# covox.net
KiCad netlist of a schematic drawn in EAGLE
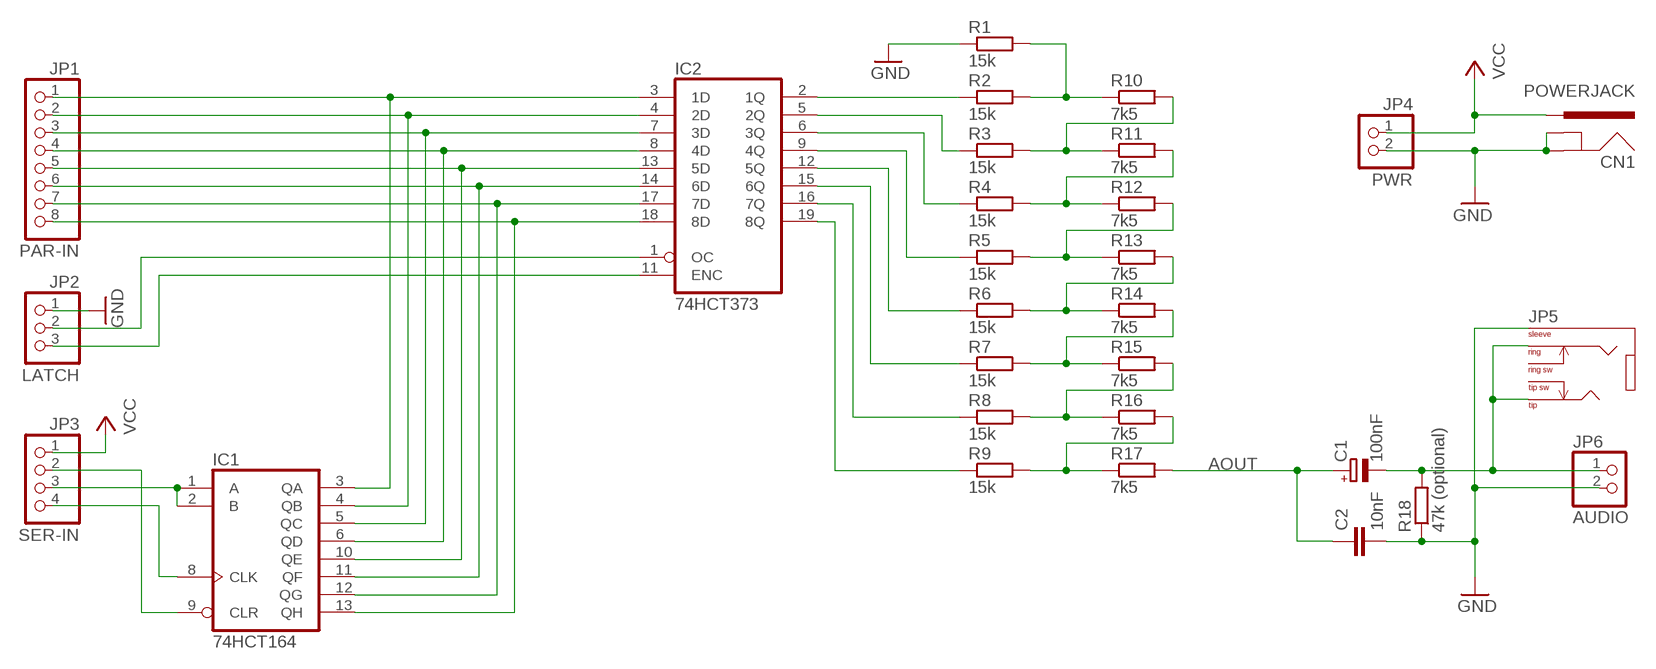
[diagram p0: schematic, sheet 1]

(export (version "E")
  (design (tool "Eeschema 10.0.6"))
  (components
    (comp (ref "C1")
      (value "100nF")
      (footprint "eagle-import:E2-4")
      (libsource (lib "eagle-import") (part "CPOL-EUE2-4"))
    )
    (comp (ref "C2")
      (value "10nF")
      (footprint "eagle-import:C025-025X050")
      (libsource (lib "eagle-import") (part "C-EU025-025X050"))
    )
    (comp (ref "CN1")
      (value "POWERJACK")
      (footprint "eagle-import:POWERJACK_SLOT")
      (libsource (lib "eagle-import") (part "POWERJACK-SLOT"))
    )
    (comp (ref "IC1")
      (value "74HCT164")
      (footprint "eagle-import:DIL14")
      (libsource (lib "eagle-import") (part "74164NHC"))
    )
    (comp (ref "IC2")
      (value "74HCT373")
      (footprint "eagle-import:DIL20")
      (libsource (lib "eagle-import") (part "74373NHCT"))
    )
    (comp (ref "JP1")
      (value "PAR-IN")
      (footprint "eagle-import:1X08")
      (libsource (lib "eagle-import") (part "PINHD-1X8"))
    )
    (comp (ref "JP2")
      (value "LATCH")
      (footprint "eagle-import:1X03")
      (libsource (lib "eagle-import") (part "PINHD-1X3"))
    )
    (comp (ref "JP3")
      (value "SER-IN")
      (footprint "eagle-import:1X04")
      (libsource (lib "eagle-import") (part "PINHD-1X4"))
    )
    (comp (ref "JP4")
      (value "PWR")
      (footprint "eagle-import:1X02")
      (libsource (lib "eagle-import") (part "PINHD-1X2"))
    )
    (comp (ref "JP5")
      (value "AUDIO")
      (footprint "eagle-import:AUDIO-JACK-3.5MM")
      (libsource (lib "eagle-import") (part "AUDIO-JACK-3.5MM"))
    )
    (comp (ref "JP6")
      (value "AUDIO")
      (footprint "eagle-import:1X02")
      (libsource (lib "eagle-import") (part "PINHD-1X2"))
    )
    (comp (ref "R1")
      (value "15k")
      (footprint "eagle-import:0204_7")
      (libsource (lib "eagle-import") (part "R-EU_0204/7"))
    )
    (comp (ref "R2")
      (value "15k")
      (footprint "eagle-import:0204_7")
      (libsource (lib "eagle-import") (part "R-EU_0204/7"))
    )
    (comp (ref "R3")
      (value "15k")
      (footprint "eagle-import:0204_7")
      (libsource (lib "eagle-import") (part "R-EU_0204/7"))
    )
    (comp (ref "R4")
      (value "15k")
      (footprint "eagle-import:0204_7")
      (libsource (lib "eagle-import") (part "R-EU_0204/7"))
    )
    (comp (ref "R5")
      (value "15k")
      (footprint "eagle-import:0204_7")
      (libsource (lib "eagle-import") (part "R-EU_0204/7"))
    )
    (comp (ref "R6")
      (value "15k")
      (footprint "eagle-import:0204_7")
      (libsource (lib "eagle-import") (part "R-EU_0204/7"))
    )
    (comp (ref "R7")
      (value "15k")
      (footprint "eagle-import:0204_7")
      (libsource (lib "eagle-import") (part "R-EU_0204/7"))
    )
    (comp (ref "R8")
      (value "15k")
      (footprint "eagle-import:0204_7")
      (libsource (lib "eagle-import") (part "R-EU_0204/7"))
    )
    (comp (ref "R9")
      (value "15k")
      (footprint "eagle-import:0204_7")
      (libsource (lib "eagle-import") (part "R-EU_0204/7"))
    )
    (comp (ref "R10")
      (value "7k5")
      (footprint "eagle-import:0204_7")
      (libsource (lib "eagle-import") (part "R-EU_0204/7"))
    )
    (comp (ref "R11")
      (value "7k5")
      (footprint "eagle-import:0204_7")
      (libsource (lib "eagle-import") (part "R-EU_0204/7"))
    )
    (comp (ref "R12")
      (value "7k5")
      (footprint "eagle-import:0204_7")
      (libsource (lib "eagle-import") (part "R-EU_0204/7"))
    )
    (comp (ref "R13")
      (value "7k5")
      (footprint "eagle-import:0204_7")
      (libsource (lib "eagle-import") (part "R-EU_0204/7"))
    )
    (comp (ref "R14")
      (value "7k5")
      (footprint "eagle-import:0204_7")
      (libsource (lib "eagle-import") (part "R-EU_0204/7"))
    )
    (comp (ref "R15")
      (value "7k5")
      (footprint "eagle-import:0204_7")
      (libsource (lib "eagle-import") (part "R-EU_0204/7"))
    )
    (comp (ref "R16")
      (value "7k5")
      (footprint "eagle-import:0204_7")
      (libsource (lib "eagle-import") (part "R-EU_0204/7"))
    )
    (comp (ref "R17")
      (value "7k5")
      (footprint "eagle-import:0204_7")
      (libsource (lib "eagle-import") (part "R-EU_0204/7"))
    )
    (comp (ref "R18")
      (value "47k (optional)")
      (footprint "eagle-import:0204_7")
      (libsource (lib "eagle-import") (part "R-EU_0204/7"))
    )
  )
  (nets
    (net (code "1") (name "/AOUT") (class "Default")
      (node (ref "C1") (pin "+") (pinfunction "+_+") (pintype "passive"))
      (node (ref "C2") (pin "1") (pinfunction "1_1") (pintype "passive"))
      (node (ref "R17") (pin "2") (pinfunction "2_2") (pintype "passive"))
    )
    (net (code "2") (name "GND") (class "Default")
      (node (ref "C2") (pin "2") (pinfunction "2_2") (pintype "passive"))
      (node (ref "CN1") (pin "GND") (pinfunction "GND_GND") (pintype "bidirectional"))
      (node (ref "CN1") (pin "GNDBREAK") (pinfunction "GNDBREAK_GNDBREAK") (pintype "bidirectional"))
      (node (ref "JP2") (pin "1") (pinfunction "1_1") (pintype "passive"))
      (node (ref "JP4") (pin "2") (pinfunction "2_2") (pintype "passive"))
      (node (ref "JP5") (pin "1") (pinfunction "1_1") (pintype "bidirectional"))
      (node (ref "JP6") (pin "2") (pinfunction "2_2") (pintype "passive"))
      (node (ref "R1") (pin "1") (pinfunction "1_1") (pintype "passive"))
      (node (ref "R18") (pin "1") (pinfunction "1_1") (pintype "passive"))
    )
    (net (code "3") (name "Net-(C1-Pad-)") (class "Default")
      (node (ref "C1") (pin "-") (pinfunction "-_-") (pintype "passive"))
      (node (ref "JP5") (pin "2") (pinfunction "2_2") (pintype "bidirectional"))
      (node (ref "JP5") (pin "3") (pinfunction "3_3") (pintype "bidirectional"))
      (node (ref "JP6") (pin "1") (pinfunction "1_1") (pintype "passive"))
      (node (ref "R18") (pin "2") (pinfunction "2_2") (pintype "passive"))
    )
    (net (code "4") (name "Net-(IC1A-A)") (class "Default")
      (node (ref "IC1") (pin "1") (pinfunction "A_1") (pintype "input"))
      (node (ref "IC1") (pin "2") (pinfunction "B_2") (pintype "input"))
      (node (ref "JP3") (pin "3") (pinfunction "3_3") (pintype "passive"))
    )
    (net (code "5") (name "Net-(IC1A-CLK)") (class "Default")
      (node (ref "IC1") (pin "8") (pinfunction "CLK_8") (pintype "input"))
      (node (ref "JP3") (pin "4") (pinfunction "4_4") (pintype "passive"))
    )
    (net (code "6") (name "Net-(IC1A-CLR)") (class "Default")
      (node (ref "IC1") (pin "9") (pinfunction "CLR_9") (pintype "input"))
      (node (ref "JP3") (pin "2") (pinfunction "2_2") (pintype "passive"))
    )
    (net (code "7") (name "Net-(IC1A-QA)") (class "Default")
      (node (ref "IC1") (pin "3") (pinfunction "QA_3") (pintype "output"))
      (node (ref "IC2") (pin "3") (pinfunction "1D_3") (pintype "input"))
      (node (ref "JP1") (pin "1") (pinfunction "1_1") (pintype "passive"))
    )
    (net (code "8") (name "Net-(IC1A-QB)") (class "Default")
      (node (ref "IC1") (pin "4") (pinfunction "QB_4") (pintype "output"))
      (node (ref "IC2") (pin "4") (pinfunction "2D_4") (pintype "input"))
      (node (ref "JP1") (pin "2") (pinfunction "2_2") (pintype "passive"))
    )
    (net (code "9") (name "Net-(IC1A-QC)") (class "Default")
      (node (ref "IC1") (pin "5") (pinfunction "QC_5") (pintype "output"))
      (node (ref "IC2") (pin "7") (pinfunction "3D_7") (pintype "input"))
      (node (ref "JP1") (pin "3") (pinfunction "3_3") (pintype "passive"))
    )
    (net (code "10") (name "Net-(IC1A-QD)") (class "Default")
      (node (ref "IC1") (pin "6") (pinfunction "QD_6") (pintype "output"))
      (node (ref "IC2") (pin "8") (pinfunction "4D_8") (pintype "input"))
      (node (ref "JP1") (pin "4") (pinfunction "4_4") (pintype "passive"))
    )
    (net (code "11") (name "Net-(IC1A-QE)") (class "Default")
      (node (ref "IC1") (pin "10") (pinfunction "QE_10") (pintype "output"))
      (node (ref "IC2") (pin "13") (pinfunction "5D_13") (pintype "input"))
      (node (ref "JP1") (pin "5") (pinfunction "5_5") (pintype "passive"))
    )
    (net (code "12") (name "Net-(IC1A-QF)") (class "Default")
      (node (ref "IC1") (pin "11") (pinfunction "QF_11") (pintype "output"))
      (node (ref "IC2") (pin "14") (pinfunction "6D_14") (pintype "input"))
      (node (ref "JP1") (pin "6") (pinfunction "6_6") (pintype "passive"))
    )
    (net (code "13") (name "Net-(IC1A-QG)") (class "Default")
      (node (ref "IC1") (pin "12") (pinfunction "QG_12") (pintype "output"))
      (node (ref "IC2") (pin "17") (pinfunction "7D_17") (pintype "input"))
      (node (ref "JP1") (pin "7") (pinfunction "7_7") (pintype "passive"))
    )
    (net (code "14") (name "Net-(IC1A-QH)") (class "Default")
      (node (ref "IC1") (pin "13") (pinfunction "QH_13") (pintype "output"))
      (node (ref "IC2") (pin "18") (pinfunction "8D_18") (pintype "input"))
      (node (ref "JP1") (pin "8") (pinfunction "8_8") (pintype "passive"))
    )
    (net (code "15") (name "Net-(IC2A-1Q)") (class "Default")
      (node (ref "IC2") (pin "2") (pinfunction "1Q_2") (pintype "tri_state"))
      (node (ref "R2") (pin "1") (pinfunction "1_1") (pintype "passive"))
    )
    (net (code "16") (name "Net-(IC2A-2Q)") (class "Default")
      (node (ref "IC2") (pin "5") (pinfunction "2Q_5") (pintype "tri_state"))
      (node (ref "R3") (pin "1") (pinfunction "1_1") (pintype "passive"))
    )
    (net (code "17") (name "Net-(IC2A-3Q)") (class "Default")
      (node (ref "IC2") (pin "6") (pinfunction "3Q_6") (pintype "tri_state"))
      (node (ref "R4") (pin "1") (pinfunction "1_1") (pintype "passive"))
    )
    (net (code "18") (name "Net-(IC2A-4Q)") (class "Default")
      (node (ref "IC2") (pin "9") (pinfunction "4Q_9") (pintype "tri_state"))
      (node (ref "R5") (pin "1") (pinfunction "1_1") (pintype "passive"))
    )
    (net (code "19") (name "Net-(IC2A-5Q)") (class "Default")
      (node (ref "IC2") (pin "12") (pinfunction "5Q_12") (pintype "tri_state"))
      (node (ref "R6") (pin "1") (pinfunction "1_1") (pintype "passive"))
    )
    (net (code "20") (name "Net-(IC2A-6Q)") (class "Default")
      (node (ref "IC2") (pin "15") (pinfunction "6Q_15") (pintype "tri_state"))
      (node (ref "R7") (pin "1") (pinfunction "1_1") (pintype "passive"))
    )
    (net (code "21") (name "Net-(IC2A-7Q)") (class "Default")
      (node (ref "IC2") (pin "16") (pinfunction "7Q_16") (pintype "tri_state"))
      (node (ref "R8") (pin "1") (pinfunction "1_1") (pintype "passive"))
    )
    (net (code "22") (name "Net-(IC2A-8Q)") (class "Default")
      (node (ref "IC2") (pin "19") (pinfunction "8Q_19") (pintype "tri_state"))
      (node (ref "R9") (pin "1") (pinfunction "1_1") (pintype "passive"))
    )
    (net (code "23") (name "Net-(IC2A-ENC)") (class "Default")
      (node (ref "IC2") (pin "11") (pinfunction "ENC_11") (pintype "input"))
      (node (ref "JP2") (pin "3") (pinfunction "3_3") (pintype "passive"))
    )
    (net (code "24") (name "Net-(IC2A-OC)") (class "Default")
      (node (ref "IC2") (pin "1") (pinfunction "OC_1") (pintype "input"))
      (node (ref "JP2") (pin "2") (pinfunction "2_2") (pintype "passive"))
    )
    (net (code "25") (name "Net-(R1-Pad2)") (class "Default")
      (node (ref "R1") (pin "2") (pinfunction "2_2") (pintype "passive"))
      (node (ref "R10") (pin "1") (pinfunction "1_1") (pintype "passive"))
      (node (ref "R2") (pin "2") (pinfunction "2_2") (pintype "passive"))
    )
    (net (code "26") (name "Net-(R10-Pad2)") (class "Default")
      (node (ref "R10") (pin "2") (pinfunction "2_2") (pintype "passive"))
      (node (ref "R11") (pin "1") (pinfunction "1_1") (pintype "passive"))
      (node (ref "R3") (pin "2") (pinfunction "2_2") (pintype "passive"))
    )
    (net (code "27") (name "Net-(R11-Pad2)") (class "Default")
      (node (ref "R11") (pin "2") (pinfunction "2_2") (pintype "passive"))
      (node (ref "R12") (pin "1") (pinfunction "1_1") (pintype "passive"))
      (node (ref "R4") (pin "2") (pinfunction "2_2") (pintype "passive"))
    )
    (net (code "28") (name "Net-(R12-Pad2)") (class "Default")
      (node (ref "R12") (pin "2") (pinfunction "2_2") (pintype "passive"))
      (node (ref "R13") (pin "1") (pinfunction "1_1") (pintype "passive"))
      (node (ref "R5") (pin "2") (pinfunction "2_2") (pintype "passive"))
    )
    (net (code "29") (name "Net-(R13-Pad2)") (class "Default")
      (node (ref "R13") (pin "2") (pinfunction "2_2") (pintype "passive"))
      (node (ref "R14") (pin "1") (pinfunction "1_1") (pintype "passive"))
      (node (ref "R6") (pin "2") (pinfunction "2_2") (pintype "passive"))
    )
    (net (code "30") (name "Net-(R14-Pad2)") (class "Default")
      (node (ref "R14") (pin "2") (pinfunction "2_2") (pintype "passive"))
      (node (ref "R15") (pin "1") (pinfunction "1_1") (pintype "passive"))
      (node (ref "R7") (pin "2") (pinfunction "2_2") (pintype "passive"))
    )
    (net (code "31") (name "Net-(R15-Pad2)") (class "Default")
      (node (ref "R15") (pin "2") (pinfunction "2_2") (pintype "passive"))
      (node (ref "R16") (pin "1") (pinfunction "1_1") (pintype "passive"))
      (node (ref "R8") (pin "2") (pinfunction "2_2") (pintype "passive"))
    )
    (net (code "32") (name "Net-(R16-Pad2)") (class "Default")
      (node (ref "R16") (pin "2") (pinfunction "2_2") (pintype "passive"))
      (node (ref "R17") (pin "1") (pinfunction "1_1") (pintype "passive"))
      (node (ref "R9") (pin "2") (pinfunction "2_2") (pintype "passive"))
    )
    (net (code "33") (name "VCC") (class "Default")
      (node (ref "CN1") (pin "PWR") (pinfunction "PWR_PWR") (pintype "bidirectional"))
      (node (ref "JP3") (pin "1") (pinfunction "1_1") (pintype "passive"))
      (node (ref "JP4") (pin "1") (pinfunction "1_1") (pintype "passive"))
    )
    (net (code "34") (name "unconnected-(JP5-Pad4)") (class "Default")
      (node (ref "JP5") (pin "4") (pinfunction "4_4") (pintype "bidirectional"))
    )
    (net (code "35") (name "unconnected-(JP5-Pad5)") (class "Default")
      (node (ref "JP5") (pin "5") (pinfunction "5_5") (pintype "bidirectional"))
    )
  )
)
